# DAC_STM32_Board_v4_-_AD5391.net
KiCad netlist of a schematic drawn in EAGLE
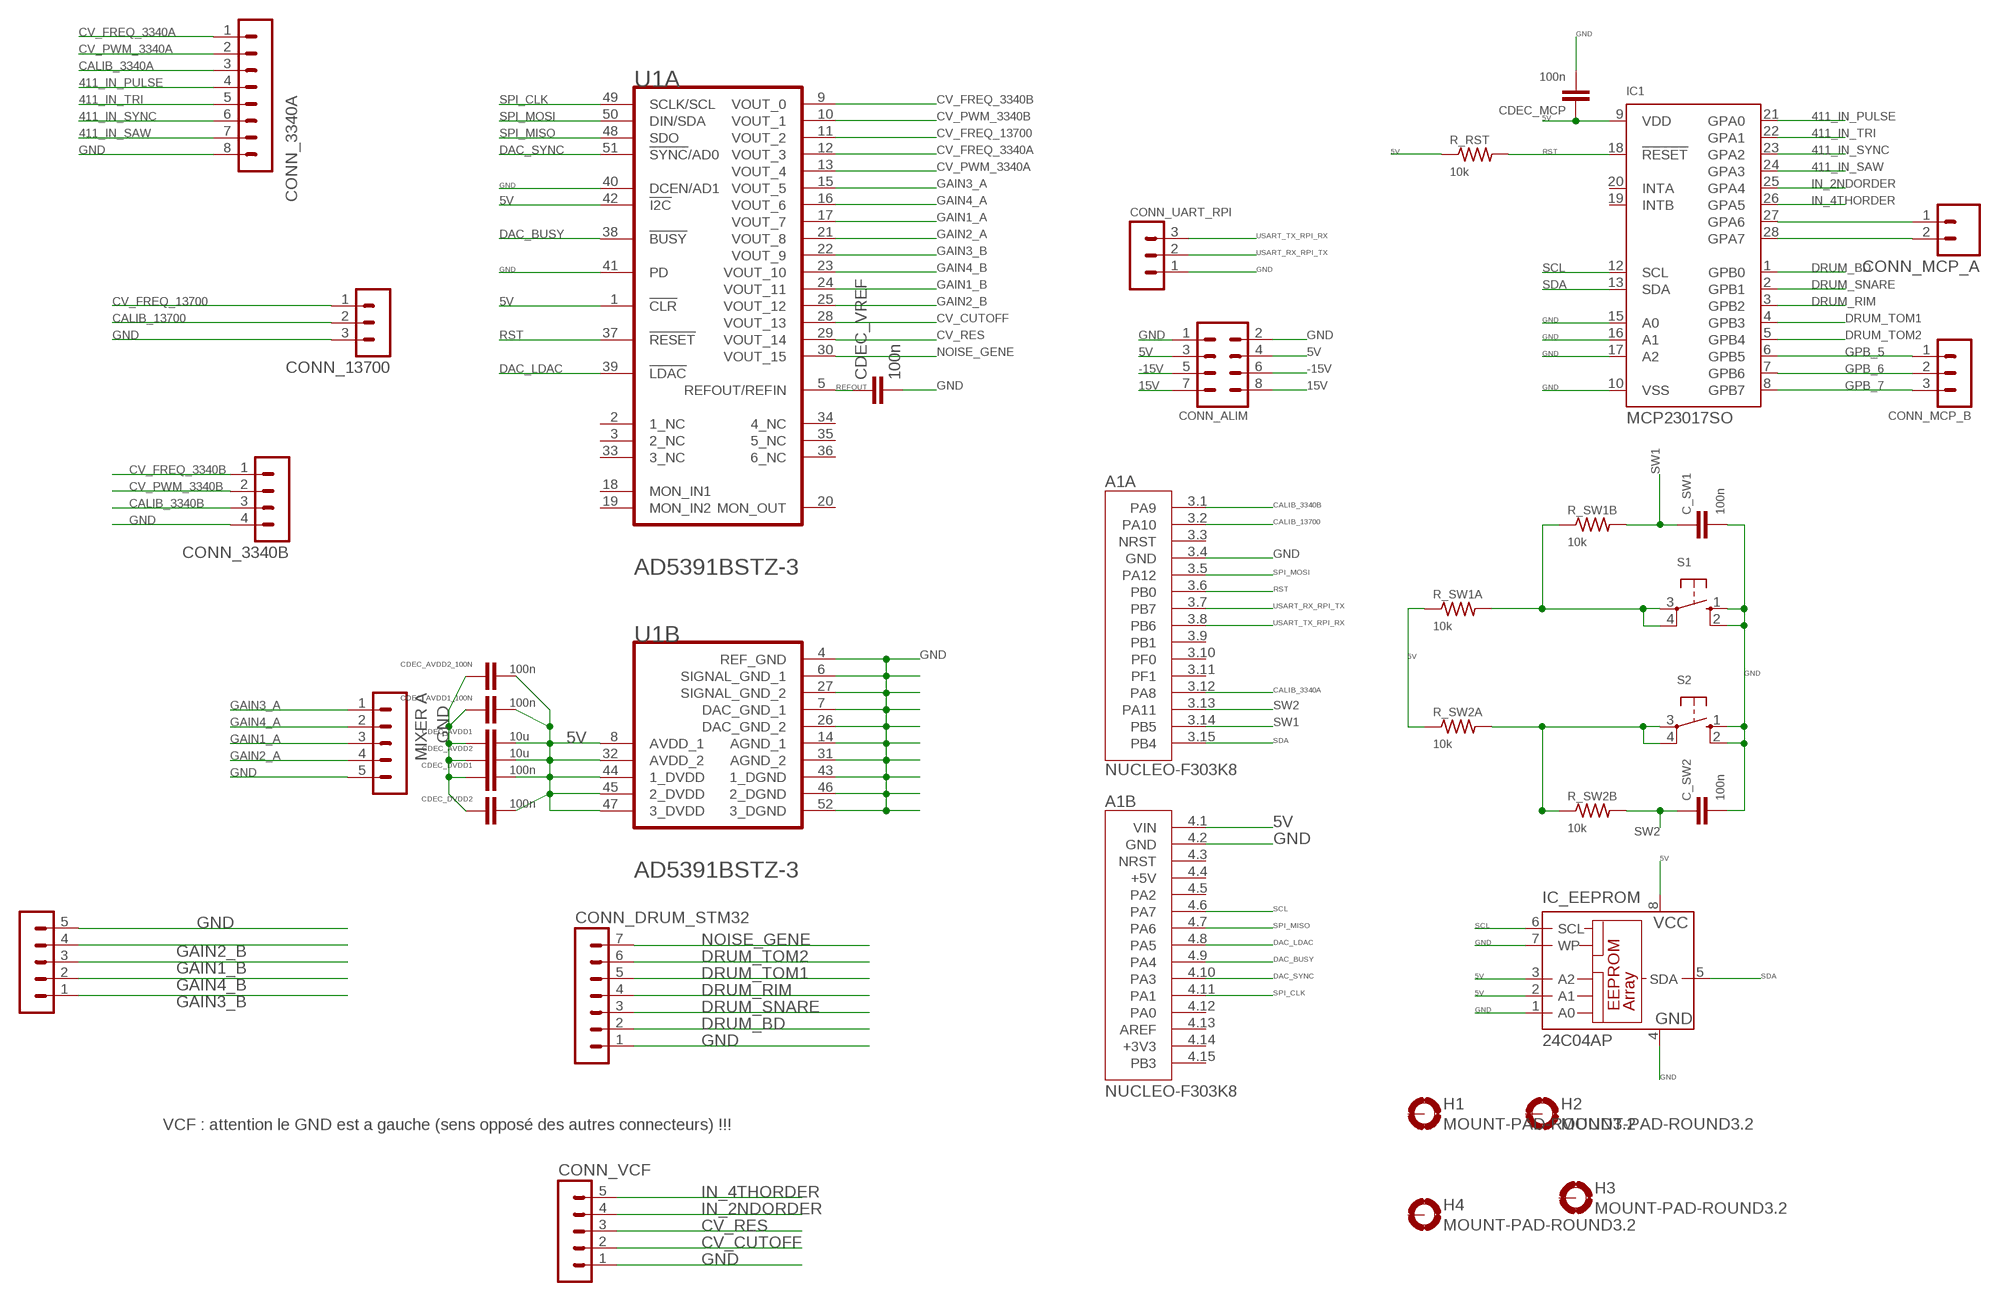
[diagram p0: schematic, sheet 1]

(export (version "E")
  (design (tool "Eeschema 10.0.6"))
  (components
    (comp (ref "A1")
      (value "NUCLEO-F303K8")
      (footprint "eagle-import:MODULE_NUCLEO-F303K8")
      (fields (field (name "DIGI-KEY_PART_NUMBER") "497-15981-ND") (field (name "MF") "STMicroelectronics"))
      (libsource (lib "eagle-import") (part "NUCLEO-F303K8"))
    )
    (comp (ref "CDEC_AVDD1")
      (value "10u")
      (footprint "eagle-import:C050-030X075")
      (libsource (lib "eagle-import") (part "C-EU050-030X075"))
    )
    (comp (ref "CDEC_AVDD1_100N")
      (value "100n")
      (footprint "eagle-import:C050-030X075")
      (libsource (lib "eagle-import") (part "C-EU050-030X075"))
    )
    (comp (ref "CDEC_AVDD2")
      (value "10u")
      (footprint "eagle-import:C050-030X075")
      (libsource (lib "eagle-import") (part "C-EU050-030X075"))
    )
    (comp (ref "CDEC_AVDD2_100N")
      (value "100n")
      (footprint "eagle-import:C050-030X075")
      (libsource (lib "eagle-import") (part "C-EU050-030X075"))
    )
    (comp (ref "CDEC_DVDD1")
      (value "100n")
      (footprint "eagle-import:C075-032X103")
      (libsource (lib "eagle-import") (part "C-EU075-032X103"))
    )
    (comp (ref "CDEC_DVDD2")
      (value "100n")
      (footprint "eagle-import:C050-030X075")
      (libsource (lib "eagle-import") (part "C-EU050-030X075"))
    )
    (comp (ref "CDEC_MCP")
      (value "100n")
      (footprint "eagle-import:C075-032X103")
      (libsource (lib "eagle-import") (part "C-EU075-032X103"))
    )
    (comp (ref "CDEC_VREF")
      (value "100n")
      (footprint "eagle-import:C050-030X075")
      (libsource (lib "eagle-import") (part "C-EU050-030X075"))
    )
    (comp (ref "CONN_3340A")
      (value "MA08-1")
      (footprint "eagle-import:MA08-1")
      (libsource (lib "eagle-import") (part "MA08-1"))
    )
    (comp (ref "CONN_3340B")
      (value "MA04-1")
      (footprint "eagle-import:MA04-1")
      (libsource (lib "eagle-import") (part "MA04-1"))
    )
    (comp (ref "CONN_13700")
      (value "MA03-1")
      (footprint "eagle-import:MA03-1")
      (libsource (lib "eagle-import") (part "MA03-1"))
    )
    (comp (ref "CONN_ALIM")
      (value "MA04-2")
      (footprint "eagle-import:MA04-2")
      (libsource (lib "eagle-import") (part "MA04-2"))
    )
    (comp (ref "CONN_DRUM_STM32")
      (value "MA07-1")
      (footprint "eagle-import:MA07-1")
      (libsource (lib "eagle-import") (part "MA07-1"))
    )
    (comp (ref "CONN_MCP_A")
      (value "M02")
      (footprint "eagle-import:02P")
      (libsource (lib "eagle-import") (part "M02"))
    )
    (comp (ref "CONN_MCP_B")
      (value "MA03-1")
      (footprint "eagle-import:MA03-1")
      (libsource (lib "eagle-import") (part "MA03-1"))
    )
    (comp (ref "CONN_MIX_A")
      (value "MA05-1")
      (footprint "eagle-import:MA05-1")
      (libsource (lib "eagle-import") (part "MA05-1"))
    )
    (comp (ref "CONN_MIX_B")
      (value "MA05-1")
      (footprint "eagle-import:MA05-1")
      (libsource (lib "eagle-import") (part "MA05-1"))
    )
    (comp (ref "CONN_UART_RPI")
      (value "MA03-1")
      (footprint "eagle-import:MA03-1")
      (libsource (lib "eagle-import") (part "MA03-1"))
    )
    (comp (ref "CONN_VCF")
      (value "MA05-1")
      (footprint "eagle-import:MA05-1")
      (libsource (lib "eagle-import") (part "MA05-1"))
    )
    (comp (ref "C_SW1")
      (value "100n")
      (footprint "eagle-import:C050-030X075")
      (libsource (lib "eagle-import") (part "C-EU050-030X075"))
    )
    (comp (ref "C_SW2")
      (value "100n")
      (footprint "eagle-import:C050-030X075")
      (libsource (lib "eagle-import") (part "C-EU050-030X075"))
    )
    (comp (ref "H1")
      (value "MOUNT-PAD-ROUND3.2")
      (footprint "eagle-import:3,2-PAD")
      (libsource (lib "eagle-import") (part "MOUNT-PAD-ROUND3.2"))
    )
    (comp (ref "H2")
      (value "MOUNT-PAD-ROUND3.2")
      (footprint "eagle-import:3,2-PAD")
      (libsource (lib "eagle-import") (part "MOUNT-PAD-ROUND3.2"))
    )
    (comp (ref "H3")
      (value "MOUNT-PAD-ROUND3.2")
      (footprint "eagle-import:3,2-PAD")
      (libsource (lib "eagle-import") (part "MOUNT-PAD-ROUND3.2"))
    )
    (comp (ref "H4")
      (value "MOUNT-PAD-ROUND3.2")
      (footprint "eagle-import:3,2-PAD")
      (libsource (lib "eagle-import") (part "MOUNT-PAD-ROUND3.2"))
    )
    (comp (ref "IC1")
      (value "MCP23017SO")
      (footprint "eagle-import:SO28W")
      (fields (field (name "MF") "MICROCHIP") (field (name "MPN") "MCP23017-E/SO"))
      (libsource (lib "eagle-import") (part "MCP23017SO"))
    )
    (comp (ref "IC_EEPROM")
      (value "24C04AP")
      (footprint "eagle-import:DIL8")
      (fields (field (name "MPN") "AT24C04B-PU"))
      (libsource (lib "eagle-import") (part "24CP04A"))
    )
    (comp (ref "R_RST")
      (value "10k")
      (footprint "eagle-import:0207_10")
      (libsource (lib "eagle-import") (part "R-US_0207/10"))
    )
    (comp (ref "R_SW1A")
      (value "10k")
      (footprint "eagle-import:0207_10")
      (libsource (lib "eagle-import") (part "R-US_0207/10"))
    )
    (comp (ref "R_SW1B")
      (value "10k")
      (footprint "eagle-import:0207_10")
      (libsource (lib "eagle-import") (part "R-US_0207/10"))
    )
    (comp (ref "R_SW2A")
      (value "10k")
      (footprint "eagle-import:0207_10")
      (libsource (lib "eagle-import") (part "R-US_0207/10"))
    )
    (comp (ref "R_SW2B")
      (value "10k")
      (footprint "eagle-import:0207_10")
      (libsource (lib "eagle-import") (part "R-US_0207/10"))
    )
    (comp (ref "S1")
      (value "10-XX")
      (footprint "eagle-import:B3F-10XX")
      (fields (field (name "MPN") "B3F-1000"))
      (libsource (lib "eagle-import") (part "10-XX"))
    )
    (comp (ref "S2")
      (value "10-XX")
      (footprint "eagle-import:B3F-10XX")
      (fields (field (name "MPN") "B3F-1000"))
      (libsource (lib "eagle-import") (part "10-XX"))
    )
    (comp (ref "U1")
      (value "ANALOG_DEVICES_AD5391BSTZ-3ANALOG_DEVICES_AD5391BSTZ-3_0_0")
      (footprint "eagle-import:ANALOG_DEVICES_AD5391BSTZ-3_0")
      (fields (field (name "MF") "Analog Devices") (field (name "MPN") "AD5391BSTZ-3"))
      (libsource (lib "eagle-import") (part "ANALOG_DEVICES_AD5391BSTZ-3ANALOG_DEVICES_AD5391BSTZ-3_0_0"))
    )
  )
  (nets
    (net (code "1") (name "/-15V") (class "Default")
      (node (ref "CONN_ALIM") (pin "5") (pinfunction "5_5") (pintype "passive"))
      (node (ref "CONN_ALIM") (pin "6") (pinfunction "6_6") (pintype "passive"))
    )
    (net (code "2") (name "/5V") (class "Default")
      (node (ref "A1") (pin "4.1") (pinfunction "VIN_4.1") (pintype "bidirectional"))
      (node (ref "CDEC_AVDD1") (pin "2") (pinfunction "2_2") (pintype "passive"))
      (node (ref "CDEC_AVDD1_100N") (pin "2") (pinfunction "2_2") (pintype "passive"))
      (node (ref "CDEC_AVDD2") (pin "2") (pinfunction "2_2") (pintype "passive"))
      (node (ref "CDEC_AVDD2_100N") (pin "2") (pinfunction "2_2") (pintype "passive"))
      (node (ref "CDEC_DVDD1") (pin "2") (pinfunction "2_2") (pintype "passive"))
      (node (ref "CDEC_DVDD2") (pin "2") (pinfunction "2_2") (pintype "passive"))
      (node (ref "CDEC_MCP") (pin "1") (pinfunction "1_1") (pintype "passive"))
      (node (ref "CONN_ALIM") (pin "3") (pinfunction "3_3") (pintype "passive"))
      (node (ref "CONN_ALIM") (pin "4") (pinfunction "4_4") (pintype "passive"))
      (node (ref "IC1") (pin "9") (pinfunction "VDD_9") (pintype "power_in"))
      (node (ref "IC_EEPROM") (pin "2") (pinfunction "A1_2") (pintype "input"))
      (node (ref "IC_EEPROM") (pin "3") (pinfunction "A2_3") (pintype "input"))
      (node (ref "IC_EEPROM") (pin "8") (pinfunction "VCC_8") (pintype "power_in"))
      (node (ref "R_RST") (pin "1") (pinfunction "1_1") (pintype "passive"))
      (node (ref "R_SW1A") (pin "1") (pinfunction "1_1") (pintype "passive"))
      (node (ref "R_SW2A") (pin "1") (pinfunction "1_1") (pintype "passive"))
      (node (ref "U1") (pin "1") (pinfunction "~{CLR}_1") (pintype "input"))
      (node (ref "U1") (pin "32") (pinfunction "AVDD_2_32") (pintype "power_in"))
      (node (ref "U1") (pin "42") (pinfunction "~{I2C}_42") (pintype "input"))
      (node (ref "U1") (pin "44") (pinfunction "1_DVDD_44") (pintype "power_in"))
      (node (ref "U1") (pin "45") (pinfunction "2_DVDD_45") (pintype "power_in"))
      (node (ref "U1") (pin "47") (pinfunction "3_DVDD_47") (pintype "power_in"))
      (node (ref "U1") (pin "8") (pinfunction "AVDD_1_8") (pintype "power_in"))
    )
    (net (code "3") (name "/15V") (class "Default")
      (node (ref "CONN_ALIM") (pin "7") (pinfunction "7_7") (pintype "passive"))
      (node (ref "CONN_ALIM") (pin "8") (pinfunction "8_8") (pintype "passive"))
    )
    (net (code "4") (name "/411_IN_PULSE") (class "Default")
      (node (ref "CONN_3340A") (pin "4") (pinfunction "4_4") (pintype "passive"))
      (node (ref "IC1") (pin "21") (pinfunction "GPA0_21") (pintype "bidirectional"))
    )
    (net (code "5") (name "/411_IN_SAW") (class "Default")
      (node (ref "CONN_3340A") (pin "7") (pinfunction "7_7") (pintype "passive"))
      (node (ref "IC1") (pin "24") (pinfunction "GPA3_24") (pintype "bidirectional"))
    )
    (net (code "6") (name "/411_IN_SYNC") (class "Default")
      (node (ref "CONN_3340A") (pin "6") (pinfunction "6_6") (pintype "passive"))
      (node (ref "IC1") (pin "23") (pinfunction "GPA2_23") (pintype "bidirectional"))
    )
    (net (code "7") (name "/411_IN_TRI") (class "Default")
      (node (ref "CONN_3340A") (pin "5") (pinfunction "5_5") (pintype "passive"))
      (node (ref "IC1") (pin "22") (pinfunction "GPA1_22") (pintype "bidirectional"))
    )
    (net (code "8") (name "/CALIB_3340A") (class "Default")
      (node (ref "A1") (pin "3.12") (pinfunction "PA8_3.12") (pintype "bidirectional"))
      (node (ref "CONN_3340A") (pin "3") (pinfunction "3_3") (pintype "passive"))
    )
    (net (code "9") (name "/CALIB_3340B") (class "Default")
      (node (ref "A1") (pin "3.1") (pinfunction "PA9_3.1") (pintype "bidirectional"))
      (node (ref "CONN_3340B") (pin "3") (pinfunction "3_3") (pintype "passive"))
    )
    (net (code "10") (name "/CALIB_13700") (class "Default")
      (node (ref "A1") (pin "3.2") (pinfunction "PA10_3.2") (pintype "bidirectional"))
      (node (ref "CONN_13700") (pin "2") (pinfunction "2_2") (pintype "passive"))
    )
    (net (code "11") (name "/CV_CUTOFF") (class "Default")
      (node (ref "CONN_VCF") (pin "2") (pinfunction "2_2") (pintype "passive"))
      (node (ref "U1") (pin "28") (pinfunction "VOUT_13_28") (pintype "tri_state"))
    )
    (net (code "12") (name "/CV_FREQ_3340A") (class "Default")
      (node (ref "CONN_3340A") (pin "1") (pinfunction "1_1") (pintype "passive"))
      (node (ref "U1") (pin "12") (pinfunction "VOUT_3_12") (pintype "tri_state"))
    )
    (net (code "13") (name "/CV_FREQ_3340B") (class "Default")
      (node (ref "CONN_3340B") (pin "1") (pinfunction "1_1") (pintype "passive"))
      (node (ref "U1") (pin "9") (pinfunction "VOUT_0_9") (pintype "tri_state"))
    )
    (net (code "14") (name "/CV_FREQ_13700") (class "Default")
      (node (ref "CONN_13700") (pin "1") (pinfunction "1_1") (pintype "passive"))
      (node (ref "U1") (pin "11") (pinfunction "VOUT_2_11") (pintype "tri_state"))
    )
    (net (code "15") (name "/CV_PWM_3340A") (class "Default")
      (node (ref "CONN_3340A") (pin "2") (pinfunction "2_2") (pintype "passive"))
      (node (ref "U1") (pin "13") (pinfunction "VOUT_4_13") (pintype "tri_state"))
    )
    (net (code "16") (name "/CV_PWM_3340B") (class "Default")
      (node (ref "CONN_3340B") (pin "2") (pinfunction "2_2") (pintype "passive"))
      (node (ref "U1") (pin "10") (pinfunction "VOUT_1_10") (pintype "tri_state"))
    )
    (net (code "17") (name "/CV_RES") (class "Default")
      (node (ref "CONN_VCF") (pin "3") (pinfunction "3_3") (pintype "passive"))
      (node (ref "U1") (pin "29") (pinfunction "VOUT_14_29") (pintype "tri_state"))
    )
    (net (code "18") (name "/DAC_BUSY") (class "Default")
      (node (ref "A1") (pin "4.9") (pinfunction "PA4_4.9") (pintype "bidirectional"))
      (node (ref "U1") (pin "38") (pinfunction "~{BUSY}_38") (pintype "output"))
    )
    (net (code "19") (name "/DAC_LDAC") (class "Default")
      (node (ref "A1") (pin "4.8") (pinfunction "PA5_4.8") (pintype "bidirectional"))
      (node (ref "U1") (pin "39") (pinfunction "~{LDAC}_39") (pintype "input"))
    )
    (net (code "20") (name "/DAC_SYNC") (class "Default")
      (node (ref "A1") (pin "4.10") (pinfunction "PA3_4.10") (pintype "bidirectional"))
      (node (ref "U1") (pin "51") (pinfunction "~{SYNC}/AD0_51") (pintype "input"))
    )
    (net (code "21") (name "/DRUM_BD") (class "Default")
      (node (ref "CONN_DRUM_STM32") (pin "2") (pinfunction "2_2") (pintype "passive"))
      (node (ref "IC1") (pin "1") (pinfunction "GPB0_1") (pintype "bidirectional"))
    )
    (net (code "22") (name "/DRUM_RIM") (class "Default")
      (node (ref "CONN_DRUM_STM32") (pin "4") (pinfunction "4_4") (pintype "passive"))
      (node (ref "IC1") (pin "3") (pinfunction "GPB2_3") (pintype "bidirectional"))
    )
    (net (code "23") (name "/DRUM_SNARE") (class "Default")
      (node (ref "CONN_DRUM_STM32") (pin "3") (pinfunction "3_3") (pintype "passive"))
      (node (ref "IC1") (pin "2") (pinfunction "GPB1_2") (pintype "bidirectional"))
    )
    (net (code "24") (name "/DRUM_TOM1") (class "Default")
      (node (ref "CONN_DRUM_STM32") (pin "5") (pinfunction "5_5") (pintype "passive"))
      (node (ref "IC1") (pin "4") (pinfunction "GPB3_4") (pintype "bidirectional"))
    )
    (net (code "25") (name "/DRUM_TOM2") (class "Default")
      (node (ref "CONN_DRUM_STM32") (pin "6") (pinfunction "6_6") (pintype "passive"))
      (node (ref "IC1") (pin "5") (pinfunction "GPB4_5") (pintype "bidirectional"))
    )
    (net (code "26") (name "/GAIN1_A") (class "Default")
      (node (ref "CONN_MIX_A") (pin "3") (pinfunction "3_3") (pintype "passive"))
      (node (ref "U1") (pin "17") (pinfunction "VOUT_7_17") (pintype "tri_state"))
    )
    (net (code "27") (name "/GAIN1_B") (class "Default")
      (node (ref "CONN_MIX_B") (pin "3") (pinfunction "3_3") (pintype "passive"))
      (node (ref "U1") (pin "24") (pinfunction "VOUT_11_24") (pintype "tri_state"))
    )
    (net (code "28") (name "/GAIN2_A") (class "Default")
      (node (ref "CONN_MIX_A") (pin "4") (pinfunction "4_4") (pintype "passive"))
      (node (ref "U1") (pin "21") (pinfunction "VOUT_8_21") (pintype "tri_state"))
    )
    (net (code "29") (name "/GAIN2_B") (class "Default")
      (node (ref "CONN_MIX_B") (pin "4") (pinfunction "4_4") (pintype "passive"))
      (node (ref "U1") (pin "25") (pinfunction "VOUT_12_25") (pintype "tri_state"))
    )
    (net (code "30") (name "/GAIN3_A") (class "Default")
      (node (ref "CONN_MIX_A") (pin "1") (pinfunction "1_1") (pintype "passive"))
      (node (ref "U1") (pin "15") (pinfunction "VOUT_5_15") (pintype "tri_state"))
    )
    (net (code "31") (name "/GAIN3_B") (class "Default")
      (node (ref "CONN_MIX_B") (pin "1") (pinfunction "1_1") (pintype "passive"))
      (node (ref "U1") (pin "22") (pinfunction "VOUT_9_22") (pintype "tri_state"))
    )
    (net (code "32") (name "/GAIN4_A") (class "Default")
      (node (ref "CONN_MIX_A") (pin "2") (pinfunction "2_2") (pintype "passive"))
      (node (ref "U1") (pin "16") (pinfunction "VOUT_6_16") (pintype "tri_state"))
    )
    (net (code "33") (name "/GAIN4_B") (class "Default")
      (node (ref "CONN_MIX_B") (pin "2") (pinfunction "2_2") (pintype "passive"))
      (node (ref "U1") (pin "23") (pinfunction "VOUT_10_23") (pintype "tri_state"))
    )
    (net (code "34") (name "/GND") (class "Default")
      (node (ref "A1") (pin "3.4") (pinfunction "GND_3.4") (pintype "bidirectional"))
      (node (ref "A1") (pin "4.2") (pinfunction "GND_4.2") (pintype "bidirectional"))
      (node (ref "CDEC_AVDD1") (pin "1") (pinfunction "1_1") (pintype "passive"))
      (node (ref "CDEC_AVDD1_100N") (pin "1") (pinfunction "1_1") (pintype "passive"))
      (node (ref "CDEC_AVDD2") (pin "1") (pinfunction "1_1") (pintype "passive"))
      (node (ref "CDEC_AVDD2_100N") (pin "1") (pinfunction "1_1") (pintype "passive"))
      (node (ref "CDEC_DVDD1") (pin "1") (pinfunction "1_1") (pintype "passive"))
      (node (ref "CDEC_DVDD2") (pin "1") (pinfunction "1_1") (pintype "passive"))
      (node (ref "CDEC_MCP") (pin "2") (pinfunction "2_2") (pintype "passive"))
      (node (ref "CDEC_VREF") (pin "2") (pinfunction "2_2") (pintype "passive"))
      (node (ref "CONN_13700") (pin "3") (pinfunction "3_3") (pintype "passive"))
      (node (ref "CONN_3340A") (pin "8") (pinfunction "8_8") (pintype "passive"))
      (node (ref "CONN_3340B") (pin "4") (pinfunction "4_4") (pintype "passive"))
      (node (ref "CONN_ALIM") (pin "1") (pinfunction "1_1") (pintype "passive"))
      (node (ref "CONN_ALIM") (pin "2") (pinfunction "2_2") (pintype "passive"))
      (node (ref "CONN_DRUM_STM32") (pin "1") (pinfunction "1_1") (pintype "passive"))
      (node (ref "CONN_MIX_A") (pin "5") (pinfunction "5_5") (pintype "passive"))
      (node (ref "CONN_MIX_B") (pin "5") (pinfunction "5_5") (pintype "passive"))
      (node (ref "CONN_UART_RPI") (pin "1") (pinfunction "1_1") (pintype "passive"))
      (node (ref "CONN_VCF") (pin "1") (pinfunction "1_1") (pintype "passive"))
      (node (ref "C_SW1") (pin "2") (pinfunction "2_2") (pintype "passive"))
      (node (ref "C_SW2") (pin "2") (pinfunction "2_2") (pintype "passive"))
      (node (ref "IC1") (pin "10") (pinfunction "VSS_10") (pintype "power_in"))
      (node (ref "IC1") (pin "15") (pinfunction "A0_15") (pintype "input"))
      (node (ref "IC1") (pin "16") (pinfunction "A1_16") (pintype "input"))
      (node (ref "IC1") (pin "17") (pinfunction "A2_17") (pintype "input"))
      (node (ref "IC_EEPROM") (pin "1") (pinfunction "A0_1") (pintype "input"))
      (node (ref "IC_EEPROM") (pin "4") (pinfunction "GND_4") (pintype "power_in"))
      (node (ref "IC_EEPROM") (pin "7") (pinfunction "WP_7") (pintype "input"))
      (node (ref "S1") (pin "1") (pinfunction "S_1") (pintype "passive"))
      (node (ref "S1") (pin "2") (pinfunction "S1_2") (pintype "passive"))
      (node (ref "S2") (pin "1") (pinfunction "S_1") (pintype "passive"))
      (node (ref "S2") (pin "2") (pinfunction "S1_2") (pintype "passive"))
      (node (ref "U1") (pin "14") (pinfunction "AGND_1_14") (pintype "power_in"))
      (node (ref "U1") (pin "26") (pinfunction "DAC_GND_2_26") (pintype "power_in"))
      (node (ref "U1") (pin "27") (pinfunction "SIGNAL_GND_2_27") (pintype "power_in"))
      (node (ref "U1") (pin "31") (pinfunction "AGND_2_31") (pintype "power_in"))
      (node (ref "U1") (pin "4") (pinfunction "REF_GND_4") (pintype "power_in"))
      (node (ref "U1") (pin "40") (pinfunction "DCEN/AD1_40") (pintype "input"))
      (node (ref "U1") (pin "41") (pinfunction "PD_41") (pintype "input"))
      (node (ref "U1") (pin "43") (pinfunction "1_DGND_43") (pintype "power_in"))
      (node (ref "U1") (pin "46") (pinfunction "2_DGND_46") (pintype "power_in"))
      (node (ref "U1") (pin "52") (pinfunction "3_DGND_52") (pintype "power_in"))
      (node (ref "U1") (pin "6") (pinfunction "SIGNAL_GND_1_6") (pintype "power_in"))
      (node (ref "U1") (pin "7") (pinfunction "DAC_GND_1_7") (pintype "power_in"))
    )
    (net (code "35") (name "/GPB_5") (class "Default")
      (node (ref "CONN_MCP_B") (pin "1") (pinfunction "1_1") (pintype "passive"))
      (node (ref "IC1") (pin "6") (pinfunction "GPB5_6") (pintype "bidirectional"))
    )
    (net (code "36") (name "/GPB_6") (class "Default")
      (node (ref "CONN_MCP_B") (pin "2") (pinfunction "2_2") (pintype "passive"))
      (node (ref "IC1") (pin "7") (pinfunction "GPB6_7") (pintype "bidirectional"))
    )
    (net (code "37") (name "/GPB_7") (class "Default")
      (node (ref "CONN_MCP_B") (pin "3") (pinfunction "3_3") (pintype "passive"))
      (node (ref "IC1") (pin "8") (pinfunction "GPB7_8") (pintype "bidirectional"))
    )
    (net (code "38") (name "/IN_2NDORDER") (class "Default")
      (node (ref "CONN_VCF") (pin "4") (pinfunction "4_4") (pintype "passive"))
      (node (ref "IC1") (pin "25") (pinfunction "GPA4_25") (pintype "bidirectional"))
    )
    (net (code "39") (name "/IN_4THORDER") (class "Default")
      (node (ref "CONN_VCF") (pin "5") (pinfunction "5_5") (pintype "passive"))
      (node (ref "IC1") (pin "26") (pinfunction "GPA5_26") (pintype "bidirectional"))
    )
    (net (code "40") (name "/NOISE_GENE") (class "Default")
      (node (ref "CONN_DRUM_STM32") (pin "7") (pinfunction "7_7") (pintype "passive"))
      (node (ref "U1") (pin "30") (pinfunction "VOUT_15_30") (pintype "tri_state"))
    )
    (net (code "41") (name "/REFOUT") (class "Default")
      (node (ref "CDEC_VREF") (pin "1") (pinfunction "1_1") (pintype "passive"))
      (node (ref "U1") (pin "5") (pinfunction "REFOUT/REFIN_5") (pintype "bidirectional"))
    )
    (net (code "42") (name "/RST") (class "Default")
      (node (ref "A1") (pin "3.6") (pinfunction "PB0_3.6") (pintype "bidirectional"))
      (node (ref "IC1") (pin "18") (pinfunction "~{RESET}_18") (pintype "input"))
      (node (ref "R_RST") (pin "2") (pinfunction "2_2") (pintype "passive"))
      (node (ref "U1") (pin "37") (pinfunction "~{RESET}_37") (pintype "input"))
    )
    (net (code "43") (name "/SCL") (class "Default")
      (node (ref "A1") (pin "4.6") (pinfunction "PA7_4.6") (pintype "bidirectional"))
      (node (ref "IC1") (pin "12") (pinfunction "SCL_12") (pintype "input"))
      (node (ref "IC_EEPROM") (pin "6") (pinfunction "SCL_6") (pintype "input"))
    )
    (net (code "44") (name "/SDA") (class "Default")
      (node (ref "A1") (pin "3.15") (pinfunction "PB4_3.15") (pintype "bidirectional"))
      (node (ref "IC1") (pin "13") (pinfunction "SDA_13") (pintype "bidirectional"))
      (node (ref "IC_EEPROM") (pin "5") (pinfunction "SDA_5") (pintype "bidirectional"))
    )
    (net (code "45") (name "/SPI_CLK") (class "Default")
      (node (ref "A1") (pin "4.11") (pinfunction "PA1_4.11") (pintype "bidirectional"))
      (node (ref "U1") (pin "49") (pinfunction "SCLK/SCL_49") (pintype "input"))
    )
    (net (code "46") (name "/SPI_MISO") (class "Default")
      (node (ref "A1") (pin "4.7") (pinfunction "PA6_4.7") (pintype "bidirectional"))
      (node (ref "U1") (pin "48") (pinfunction "SDO_48") (pintype "tri_state"))
    )
    (net (code "47") (name "/SPI_MOSI") (class "Default")
      (node (ref "A1") (pin "3.5") (pinfunction "PA12_3.5") (pintype "bidirectional"))
      (node (ref "U1") (pin "50") (pinfunction "DIN/SDA_50") (pintype "bidirectional"))
    )
    (net (code "48") (name "/SW1") (class "Default")
      (node (ref "A1") (pin "3.14") (pinfunction "PB5_3.14") (pintype "bidirectional"))
      (node (ref "C_SW1") (pin "1") (pinfunction "1_1") (pintype "passive"))
      (node (ref "R_SW1B") (pin "2") (pinfunction "2_2") (pintype "passive"))
    )
    (net (code "49") (name "/SW2") (class "Default")
      (node (ref "A1") (pin "3.13") (pinfunction "PA11_3.13") (pintype "bidirectional"))
      (node (ref "C_SW2") (pin "1") (pinfunction "1_1") (pintype "passive"))
      (node (ref "R_SW2B") (pin "2") (pinfunction "2_2") (pintype "passive"))
    )
    (net (code "50") (name "/USART_RX_RPI_TX") (class "Default")
      (node (ref "A1") (pin "3.7") (pinfunction "PB7_3.7") (pintype "bidirectional"))
      (node (ref "CONN_UART_RPI") (pin "2") (pinfunction "2_2") (pintype "passive"))
    )
    (net (code "51") (name "/USART_TX_RPI_RX") (class "Default")
      (node (ref "A1") (pin "3.8") (pinfunction "PB6_3.8") (pintype "bidirectional"))
      (node (ref "CONN_UART_RPI") (pin "3") (pinfunction "3_3") (pintype "passive"))
    )
    (net (code "52") (name "Net-(IC1-GPA6)") (class "Default")
      (node (ref "CONN_MCP_A") (pin "1") (pinfunction "1_1") (pintype "passive"))
      (node (ref "IC1") (pin "27") (pinfunction "GPA6_27") (pintype "bidirectional"))
    )
    (net (code "53") (name "Net-(IC1-GPA7)") (class "Default")
      (node (ref "CONN_MCP_A") (pin "2") (pinfunction "2_2") (pintype "passive"))
      (node (ref "IC1") (pin "28") (pinfunction "GPA7_28") (pintype "bidirectional"))
    )
    (net (code "54") (name "Net-(S1-P)") (class "Default")
      (node (ref "R_SW1A") (pin "2") (pinfunction "2_2") (pintype "passive"))
      (node (ref "R_SW1B") (pin "1") (pinfunction "1_1") (pintype "passive"))
      (node (ref "S1") (pin "3") (pinfunction "P_3") (pintype "passive"))
      (node (ref "S1") (pin "4") (pinfunction "P1_4") (pintype "passive"))
    )
    (net (code "55") (name "Net-(S2-P)") (class "Default")
      (node (ref "R_SW2A") (pin "2") (pinfunction "2_2") (pintype "passive"))
      (node (ref "R_SW2B") (pin "1") (pinfunction "1_1") (pintype "passive"))
      (node (ref "S2") (pin "3") (pinfunction "P_3") (pintype "passive"))
      (node (ref "S2") (pin "4") (pinfunction "P1_4") (pintype "passive"))
    )
    (net (code "56") (name "unconnected-(A1A-NRST-Pad3.3)") (class "Default")
      (node (ref "A1") (pin "3.3") (pinfunction "NRST_3.3") (pintype "bidirectional"))
    )
    (net (code "57") (name "unconnected-(A1A-PB1-Pad3.9)") (class "Default")
      (node (ref "A1") (pin "3.9") (pinfunction "PB1_3.9") (pintype "bidirectional"))
    )
    (net (code "58") (name "unconnected-(A1A-PF0-Pad3.10)") (class "Default")
      (node (ref "A1") (pin "3.10") (pinfunction "PF0_3.10") (pintype "bidirectional"))
    )
    (net (code "59") (name "unconnected-(A1A-PF1-Pad3.11)") (class "Default")
      (node (ref "A1") (pin "3.11") (pinfunction "PF1_3.11") (pintype "bidirectional"))
    )
    (net (code "60") (name "unconnected-(A1B-+3V3-Pad4.14)") (class "Default")
      (node (ref "A1") (pin "4.14") (pinfunction "+3V3_4.14") (pintype "bidirectional"))
    )
    (net (code "61") (name "unconnected-(A1B-+5V-Pad4.4)") (class "Default")
      (node (ref "A1") (pin "4.4") (pinfunction "+5V_4.4") (pintype "bidirectional"))
    )
    (net (code "62") (name "unconnected-(A1B-AREF-Pad4.13)") (class "Default")
      (node (ref "A1") (pin "4.13") (pinfunction "AREF_4.13") (pintype "bidirectional"))
    )
    (net (code "63") (name "unconnected-(A1B-NRST-Pad4.3)") (class "Default")
      (node (ref "A1") (pin "4.3") (pinfunction "NRST_4.3") (pintype "bidirectional"))
    )
    (net (code "64") (name "unconnected-(A1B-PA0-Pad4.12)") (class "Default")
      (node (ref "A1") (pin "4.12") (pinfunction "PA0_4.12") (pintype "bidirectional"))
    )
    (net (code "65") (name "unconnected-(A1B-PA2-Pad4.5)") (class "Default")
      (node (ref "A1") (pin "4.5") (pinfunction "PA2_4.5") (pintype "bidirectional"))
    )
    (net (code "66") (name "unconnected-(A1B-PB3-Pad4.15)") (class "Default")
      (node (ref "A1") (pin "4.15") (pinfunction "PB3_4.15") (pintype "bidirectional"))
    )
    (net (code "67") (name "unconnected-(H1-MOUNT-PadB3,2)") (class "Default")
      (node (ref "H1") (pin "B3,2") (pinfunction "MOUNT_B3,2") (pintype "passive"))
    )
    (net (code "68") (name "unconnected-(H2-MOUNT-PadB3,2)") (class "Default")
      (node (ref "H2") (pin "B3,2") (pinfunction "MOUNT_B3,2") (pintype "passive"))
    )
    (net (code "69") (name "unconnected-(H3-MOUNT-PadB3,2)") (class "Default")
      (node (ref "H3") (pin "B3,2") (pinfunction "MOUNT_B3,2") (pintype "passive"))
    )
    (net (code "70") (name "unconnected-(H4-MOUNT-PadB3,2)") (class "Default")
      (node (ref "H4") (pin "B3,2") (pinfunction "MOUNT_B3,2") (pintype "passive"))
    )
    (net (code "71") (name "unconnected-(IC1-INTA-Pad20)") (class "Default")
      (node (ref "IC1") (pin "20") (pinfunction "INTA_20") (pintype "output"))
    )
    (net (code "72") (name "unconnected-(IC1-INTB-Pad19)") (class "Default")
      (node (ref "IC1") (pin "19") (pinfunction "INTB_19") (pintype "output"))
    )
    (net (code "73") (name "unconnected-(U1A-1_NC-Pad2)") (class "Default")
      (node (ref "U1") (pin "2") (pinfunction "1_NC_2") (pintype "passive"))
    )
    (net (code "74") (name "unconnected-(U1A-2_NC-Pad3)") (class "Default")
      (node (ref "U1") (pin "3") (pinfunction "2_NC_3") (pintype "passive"))
    )
    (net (code "75") (name "unconnected-(U1A-3_NC-Pad33)") (class "Default")
      (node (ref "U1") (pin "33") (pinfunction "3_NC_33") (pintype "passive"))
    )
    (net (code "76") (name "unconnected-(U1A-4_NC-Pad34)") (class "Default")
      (node (ref "U1") (pin "34") (pinfunction "4_NC_34") (pintype "passive"))
    )
    (net (code "77") (name "unconnected-(U1A-5_NC-Pad35)") (class "Default")
      (node (ref "U1") (pin "35") (pinfunction "5_NC_35") (pintype "passive"))
    )
    (net (code "78") (name "unconnected-(U1A-6_NC-Pad36)") (class "Default")
      (node (ref "U1") (pin "36") (pinfunction "6_NC_36") (pintype "passive"))
    )
    (net (code "79") (name "unconnected-(U1A-MON_IN1-Pad18)") (class "Default")
      (node (ref "U1") (pin "18") (pinfunction "MON_IN1_18") (pintype "input"))
    )
    (net (code "80") (name "unconnected-(U1A-MON_IN2-Pad19)") (class "Default")
      (node (ref "U1") (pin "19") (pinfunction "MON_IN2_19") (pintype "input"))
    )
    (net (code "81") (name "unconnected-(U1A-MON_OUT-Pad20)") (class "Default")
      (node (ref "U1") (pin "20") (pinfunction "MON_OUT_20") (pintype "tri_state"))
    )
  )
)
